# esp_LedControl.net
KiCad netlist of a schematic drawn in EAGLE
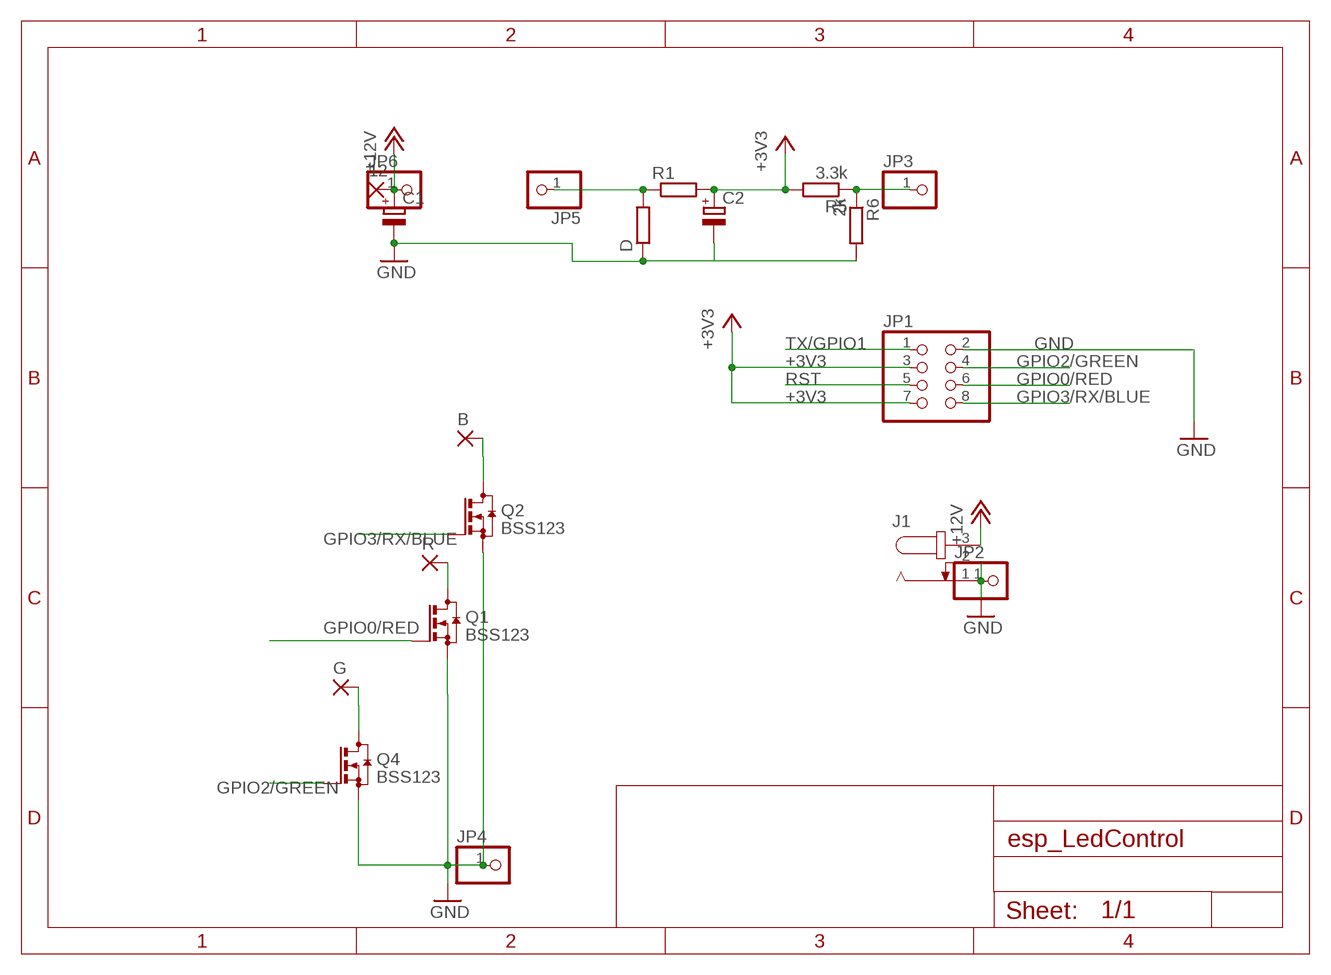
[diagram p0: schematic, sheet 1]

(export (version "E")
  (design (tool "Eeschema 10.0.6"))
  (components
    (comp (ref "12")
      (value "3,17/1,3")
      (footprint "eagle-import:3,17_1,3")
      (libsource (lib "eagle-import") (part "3,17/1,3"))
    )
    (comp (ref "B")
      (value "3,17/1,3")
      (footprint "eagle-import:3,17_1,3")
      (libsource (lib "eagle-import") (part "3,17/1,3"))
    )
    (comp (ref "C1")
      (value "CPOL-EUE2.5-5")
      (footprint "eagle-import:E2,5-5")
      (libsource (lib "eagle-import") (part "CPOL-EUE2.5-5"))
    )
    (comp (ref "C2")
      (value "CPOL-EUE2.5-5")
      (footprint "eagle-import:E2,5-5")
      (libsource (lib "eagle-import") (part "CPOL-EUE2.5-5"))
    )
    (comp (ref "D")
      (value "R-EU_0204/7")
      (footprint "eagle-import:0204_7")
      (libsource (lib "eagle-import") (part "R-EU_0204/7"))
    )
    (comp (ref "G")
      (value "3,17/1,3")
      (footprint "eagle-import:3,17_1,3")
      (libsource (lib "eagle-import") (part "3,17/1,3"))
    )
    (comp (ref "J1")
      (value "JACK-PLUG0")
      (footprint "eagle-import:SPC4077")
      (libsource (lib "eagle-import") (part "JACK-PLUG0"))
    )
    (comp (ref "JP1")
      (value "PINHD-2X4")
      (footprint "eagle-import:2X04")
      (libsource (lib "eagle-import") (part "PINHD-2X4"))
    )
    (comp (ref "JP2")
      (value "PINHD-1X1")
      (footprint "eagle-import:1X01")
      (libsource (lib "eagle-import") (part "PINHD-1X1"))
    )
    (comp (ref "JP3")
      (value "PINHD-1X1")
      (footprint "eagle-import:1X01")
      (libsource (lib "eagle-import") (part "PINHD-1X1"))
    )
    (comp (ref "JP4")
      (value "PINHD-1X1")
      (footprint "eagle-import:1X01")
      (libsource (lib "eagle-import") (part "PINHD-1X1"))
    )
    (comp (ref "JP5")
      (value "PINHD-1X1")
      (footprint "eagle-import:1X01")
      (libsource (lib "eagle-import") (part "PINHD-1X1"))
    )
    (comp (ref "JP6")
      (value "PINHD-1X1")
      (footprint "eagle-import:1X01")
      (libsource (lib "eagle-import") (part "PINHD-1X1"))
    )
    (comp (ref "Q1")
      (value "BSS123")
      (footprint "eagle-import:SOT23")
      (libsource (lib "eagle-import") (part "BSS123"))
    )
    (comp (ref "Q2")
      (value "BSS123")
      (footprint "eagle-import:SOT23")
      (libsource (lib "eagle-import") (part "BSS123"))
    )
    (comp (ref "Q4")
      (value "BSS123")
      (footprint "eagle-import:SOT23")
      (libsource (lib "eagle-import") (part "BSS123"))
    )
    (comp (ref "R")
      (value "3,17/1,3")
      (footprint "eagle-import:3,17_1,3")
      (libsource (lib "eagle-import") (part "3,17/1,3"))
    )
    (comp (ref "R1")
      (value "R-EU_0204/7")
      (footprint "eagle-import:0204_7")
      (libsource (lib "eagle-import") (part "R-EU_0204/7"))
    )
    (comp (ref "R5")
      (value "3.3k")
      (footprint "eagle-import:R0805")
      (libsource (lib "eagle-import") (part "R-EU_R0805"))
    )
    (comp (ref "R6")
      (value "2k")
      (footprint "eagle-import:R0805")
      (libsource (lib "eagle-import") (part "R-EU_R0805"))
    )
  )
  (nets
    (net (code "1") (name "+3V3") (class "Default")
      (node (ref "C2") (pin "+") (pinfunction "+_+") (pintype "passive"))
      (node (ref "JP1") (pin "3") (pinfunction "3_3") (pintype "passive"))
      (node (ref "JP1") (pin "7") (pinfunction "7_7") (pintype "passive"))
      (node (ref "R1") (pin "2") (pinfunction "2_2") (pintype "passive"))
      (node (ref "R5") (pin "2") (pinfunction "2_2") (pintype "passive"))
    )
    (net (code "2") (name "+12V") (class "Default")
      (node (ref "12") (pin "1") (pinfunction "P_1") (pintype "passive"))
      (node (ref "C1") (pin "+") (pinfunction "+_+") (pintype "passive"))
      (node (ref "J1") (pin "3") (pinfunction "3_3") (pintype "passive"))
      (node (ref "JP6") (pin "1") (pinfunction "1_1") (pintype "passive"))
    )
    (net (code "3") (name "/GPIO0{slash}RED") (class "Default")
      (node (ref "JP1") (pin "6") (pinfunction "6_6") (pintype "passive"))
      (node (ref "Q1") (pin "1") (pinfunction "G_1") (pintype "passive"))
    )
    (net (code "4") (name "/GPIO2{slash}GREEN") (class "Default")
      (node (ref "JP1") (pin "4") (pinfunction "4_4") (pintype "passive"))
      (node (ref "Q4") (pin "1") (pinfunction "G_1") (pintype "passive"))
    )
    (net (code "5") (name "/GPIO3{slash}RX{slash}BLUE") (class "Default")
      (node (ref "JP1") (pin "8") (pinfunction "8_8") (pintype "passive"))
      (node (ref "Q2") (pin "1") (pinfunction "G_1") (pintype "passive"))
    )
    (net (code "6") (name "/RST") (class "Default")
      (node (ref "JP1") (pin "5") (pinfunction "5_5") (pintype "passive"))
    )
    (net (code "7") (name "/TX{slash}GPIO1") (class "Default")
      (node (ref "JP1") (pin "1") (pinfunction "1_1") (pintype "passive"))
    )
    (net (code "8") (name "GND") (class "Default")
      (node (ref "C1") (pin "-") (pinfunction "-_-") (pintype "passive"))
      (node (ref "C2") (pin "-") (pinfunction "-_-") (pintype "passive"))
      (node (ref "D") (pin "1") (pinfunction "1_1") (pintype "passive"))
      (node (ref "J1") (pin "1") (pinfunction "1_1") (pintype "passive"))
      (node (ref "J1") (pin "2") (pinfunction "2_2") (pintype "passive"))
      (node (ref "JP1") (pin "2") (pinfunction "2_2") (pintype "passive"))
      (node (ref "JP2") (pin "1") (pinfunction "1_1") (pintype "passive"))
      (node (ref "JP4") (pin "1") (pinfunction "1_1") (pintype "passive"))
      (node (ref "Q1") (pin "2") (pinfunction "S_2") (pintype "passive"))
      (node (ref "Q2") (pin "2") (pinfunction "S_2") (pintype "passive"))
      (node (ref "Q4") (pin "2") (pinfunction "S_2") (pintype "passive"))
      (node (ref "R6") (pin "2") (pinfunction "2_2") (pintype "passive"))
    )
    (net (code "9") (name "Net-(B-P)") (class "Default")
      (node (ref "B") (pin "1") (pinfunction "P_1") (pintype "passive"))
      (node (ref "Q2") (pin "3") (pinfunction "D_3") (pintype "passive"))
    )
    (net (code "10") (name "Net-(D-Pad2)") (class "Default")
      (node (ref "D") (pin "2") (pinfunction "2_2") (pintype "passive"))
      (node (ref "JP5") (pin "1") (pinfunction "1_1") (pintype "passive"))
      (node (ref "R1") (pin "1") (pinfunction "1_1") (pintype "passive"))
    )
    (net (code "11") (name "Net-(G-P)") (class "Default")
      (node (ref "G") (pin "1") (pinfunction "P_1") (pintype "passive"))
      (node (ref "Q4") (pin "3") (pinfunction "D_3") (pintype "passive"))
    )
    (net (code "12") (name "Net-(JP3-Pad1)") (class "Default")
      (node (ref "JP3") (pin "1") (pinfunction "1_1") (pintype "passive"))
      (node (ref "R5") (pin "1") (pinfunction "1_1") (pintype "passive"))
      (node (ref "R6") (pin "1") (pinfunction "1_1") (pintype "passive"))
    )
    (net (code "13") (name "Net-(Q1-D)") (class "Default")
      (node (ref "Q1") (pin "3") (pinfunction "D_3") (pintype "passive"))
      (node (ref "R") (pin "1") (pinfunction "P_1") (pintype "passive"))
    )
  )
)
